# Qwiic_KX134.net
KiCad netlist of a schematic drawn in EAGLE
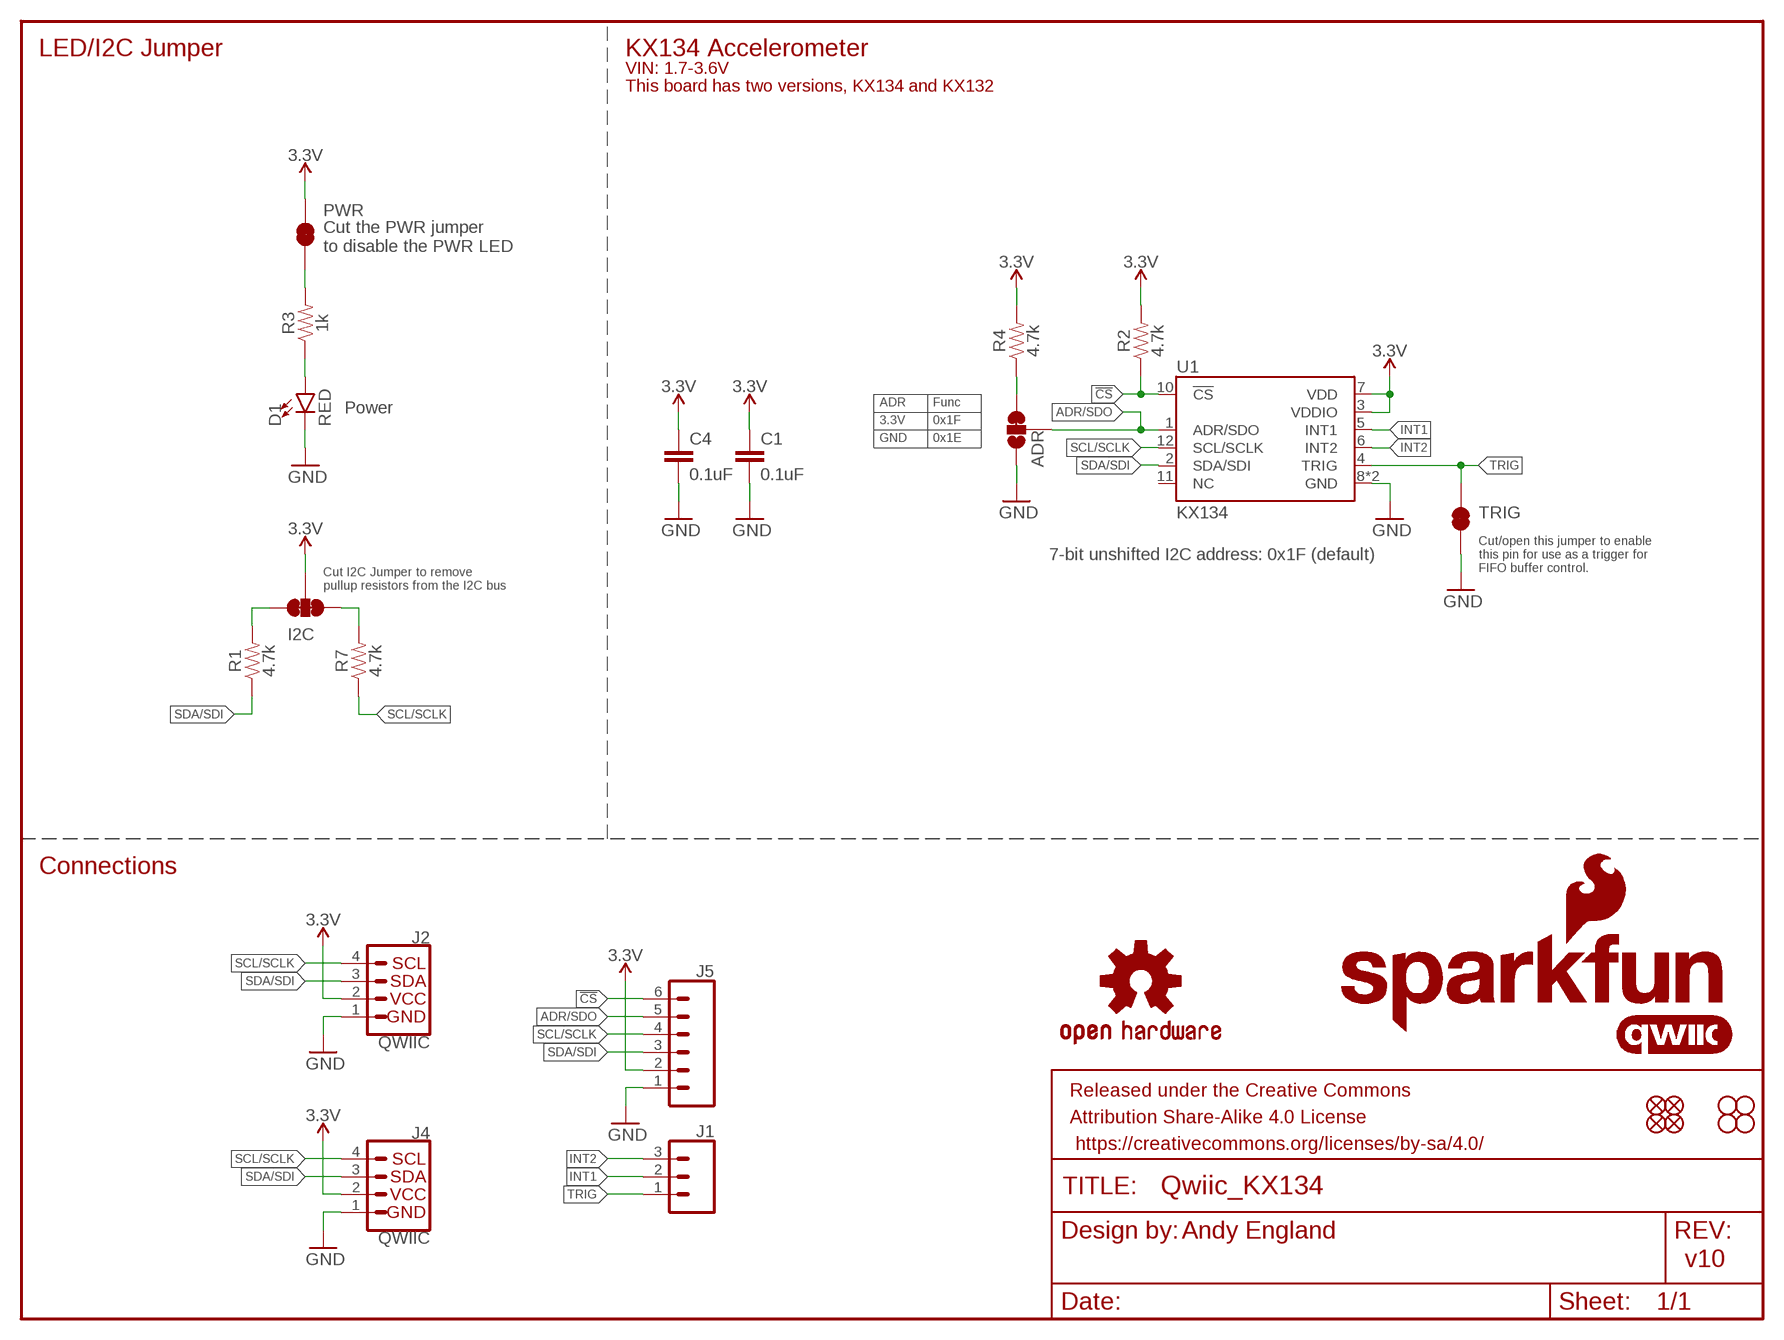
[diagram p0: schematic, sheet 1]

(export (version "E")
  (design (tool "Eeschema 10.0.6"))
  (components
    (comp (ref "ADR")
      (value "JUMPER-SMT_3_1-NC_TRACE_SILK")
      (footprint "eagle-import:SMT-JUMPER_3_1-NC_TRACE_SILK")
      (libsource (lib "eagle-import") (part "JUMPER-SMT_3_1-NC_TRACE_SILK"))
    )
    (comp (ref "C1")
      (value "0.1uF")
      (footprint "eagle-import:0603")
      (libsource (lib "eagle-import") (part "0.1UF-0603-25V-(+80/-20%)"))
    )
    (comp (ref "C4")
      (value "0.1uF")
      (footprint "eagle-import:0603")
      (libsource (lib "eagle-import") (part "0.1UF-0603-25V-(+80/-20%)"))
    )
    (comp (ref "D1")
      (value "RED")
      (footprint "eagle-import:LED-0603")
      (libsource (lib "eagle-import") (part "LED-RED0603"))
    )
    (comp (ref "FRAME1")
      (value "FRAME-LETTER")
      (footprint "eagle-import:CREATIVE_COMMONS")
      (libsource (lib "eagle-import") (part "FRAME-LETTER"))
    )
    (comp (ref "I2C")
      (value "JUMPER-SMT_3_2-NC_TRACE_SILK")
      (footprint "eagle-import:SMT-JUMPER_3_2-NC_TRACE_SILK")
      (libsource (lib "eagle-import") (part "JUMPER-SMT_3_2-NC_TRACE_SILK"))
    )
    (comp (ref "J1")
      (value "CONN_031X03_NO_SILK")
      (footprint "eagle-import:1X03_NO_SILK")
      (libsource (lib "eagle-import") (part "CONN_031X03_NO_SILK"))
    )
    (comp (ref "J2")
      (value "QWIIC")
      (footprint "eagle-import:JST04_1MM_RA")
      (libsource (lib "eagle-import") (part "QWIIC_CONNECTORJS-1MM"))
    )
    (comp (ref "J4")
      (value "QWIIC")
      (footprint "eagle-import:JST04_1MM_RA")
      (libsource (lib "eagle-import") (part "QWIIC_CONNECTORJS-1MM"))
    )
    (comp (ref "J5")
      (value "CONN_06NO_SILK_NO_POP")
      (footprint "eagle-import:1X06_NO_SILK")
      (libsource (lib "eagle-import") (part "CONN_06NO_SILK_NO_POP"))
    )
    (comp (ref "JP1")
      (value "FIDUCIALUFIDUCIAL")
      (footprint "eagle-import:MICRO-FIDUCIAL")
      (libsource (lib "eagle-import") (part "FIDUCIALUFIDUCIAL"))
    )
    (comp (ref "JP2")
      (value "FIDUCIALUFIDUCIAL")
      (footprint "eagle-import:MICRO-FIDUCIAL")
      (libsource (lib "eagle-import") (part "FIDUCIALUFIDUCIAL"))
    )
    (comp (ref "JP3")
      (value "STAND-OFF")
      (footprint "eagle-import:STAND-OFF")
      (libsource (lib "eagle-import") (part "STAND-OFF"))
    )
    (comp (ref "JP4")
      (value "STAND-OFF")
      (footprint "eagle-import:STAND-OFF")
      (libsource (lib "eagle-import") (part "STAND-OFF"))
    )
    (comp (ref "JP5")
      (value "FIDUCIALUFIDUCIAL")
      (footprint "eagle-import:MICRO-FIDUCIAL")
      (libsource (lib "eagle-import") (part "FIDUCIALUFIDUCIAL"))
    )
    (comp (ref "JP6")
      (value "FIDUCIALUFIDUCIAL")
      (footprint "eagle-import:MICRO-FIDUCIAL")
      (libsource (lib "eagle-import") (part "FIDUCIALUFIDUCIAL"))
    )
    (comp (ref "JP7")
      (value "STAND-OFF")
      (footprint "eagle-import:STAND-OFF")
      (libsource (lib "eagle-import") (part "STAND-OFF"))
    )
    (comp (ref "JP8")
      (value "STAND-OFF")
      (footprint "eagle-import:STAND-OFF")
      (libsource (lib "eagle-import") (part "STAND-OFF"))
    )
    (comp (ref "LOGO1")
      (value "SFE_LOGO_FLAME.1_INCH")
      (footprint "eagle-import:SFE_LOGO_FLAME_.1")
      (libsource (lib "eagle-import") (part "SFE_LOGO_FLAME.1_INCH"))
    )
    (comp (ref "LOGO2")
      (value "SFE_LOGO_FLAME.1_INCH")
      (footprint "eagle-import:SFE_LOGO_FLAME_.1")
      (libsource (lib "eagle-import") (part "SFE_LOGO_FLAME.1_INCH"))
    )
    (comp (ref "LOGO3")
      (value "QWIIC_LOGO_4MM")
      (footprint "eagle-import:QWIIC_4MM")
      (libsource (lib "eagle-import") (part "QWIIC_LOGO_4MM"))
    )
    (comp (ref "LOGO4")
      (value "SFE_LOGO_NAME_FLAME.1_INCH")
      (footprint "eagle-import:SFE_LOGO_NAME_FLAME_.1")
      (libsource (lib "eagle-import") (part "SFE_LOGO_NAME_FLAME.1_INCH"))
    )
    (comp (ref "LOGO5")
      (value "OSHW-LOGOS")
      (footprint "eagle-import:OSHW-LOGO-S")
      (libsource (lib "eagle-import") (part "OSHW-LOGOS"))
    )
    (comp (ref "PWR")
      (value "JUMPER-SMT_2_NC_TRACE_SILK")
      (footprint "eagle-import:SMT-JUMPER_2_NC_TRACE_SILK")
      (libsource (lib "eagle-import") (part "JUMPER-SMT_2_NC_TRACE_SILK"))
    )
    (comp (ref "R1")
      (value "4.7k")
      (footprint "eagle-import:0603")
      (libsource (lib "eagle-import") (part "4.7KOHM-0603-1/10W-1%"))
    )
    (comp (ref "R2")
      (value "4.7k")
      (footprint "eagle-import:0603")
      (libsource (lib "eagle-import") (part "4.7KOHM-0603-1/10W-1%"))
    )
    (comp (ref "R3")
      (value "1k")
      (footprint "eagle-import:0603")
      (libsource (lib "eagle-import") (part "1KOHM-0603-1/10W-1%"))
    )
    (comp (ref "R4")
      (value "4.7k")
      (footprint "eagle-import:0603")
      (libsource (lib "eagle-import") (part "4.7KOHM-0603-1/10W-1%"))
    )
    (comp (ref "R7")
      (value "4.7k")
      (footprint "eagle-import:0603")
      (libsource (lib "eagle-import") (part "4.7KOHM-0603-1/10W-1%"))
    )
    (comp (ref "TRIG")
      (value "JUMPER-SMT_2_NC_TRACE_SILK")
      (footprint "eagle-import:SMT-JUMPER_2_NC_TRACE_SILK")
      (libsource (lib "eagle-import") (part "JUMPER-SMT_2_NC_TRACE_SILK"))
    )
    (comp (ref "U1")
      (value "KX134")
      (footprint "eagle-import:KX13X")
      (libsource (lib "eagle-import") (part "KX13X-KX134"))
    )
  )
  (nets
    (net (code "1") (name "/~{CS}") (class "Default")
      (node (ref "J5") (pin "6") (pinfunction "6_6") (pintype "passive"))
      (node (ref "R2") (pin "1") (pinfunction "1_1") (pintype "passive"))
      (node (ref "U1") (pin "10") (pinfunction "~{CS}_10") (pintype "bidirectional"))
    )
    (net (code "2") (name "3.3V") (class "Default")
      (node (ref "C1") (pin "1") (pinfunction "1_1") (pintype "passive"))
      (node (ref "C4") (pin "1") (pinfunction "1_1") (pintype "passive"))
      (node (ref "I2C") (pin "2") (pinfunction "2_2") (pintype "passive"))
      (node (ref "J2") (pin "2") (pinfunction "2_2") (pintype "power_in"))
      (node (ref "J4") (pin "2") (pinfunction "2_2") (pintype "power_in"))
      (node (ref "J5") (pin "2") (pinfunction "2_2") (pintype "passive"))
      (node (ref "PWR") (pin "2") (pinfunction "2_2") (pintype "passive"))
      (node (ref "R2") (pin "2") (pinfunction "2_2") (pintype "passive"))
      (node (ref "R4") (pin "2") (pinfunction "2_2") (pintype "passive"))
      (node (ref "U1") (pin "3") (pinfunction "VDDIO_3") (pintype "bidirectional"))
      (node (ref "U1") (pin "7") (pinfunction "VDD_7") (pintype "bidirectional"))
    )
    (net (code "3") (name "ADR{slash}SDO") (class "Default")
      (node (ref "ADR") (pin "2") (pinfunction "2_2") (pintype "passive"))
      (node (ref "J5") (pin "5") (pinfunction "5_5") (pintype "passive"))
      (node (ref "U1") (pin "1") (pinfunction "ADR/SDO_1") (pintype "bidirectional"))
    )
    (net (code "4") (name "GND") (class "Default")
      (node (ref "ADR") (pin "1") (pinfunction "1_1") (pintype "passive"))
      (node (ref "C1") (pin "2") (pinfunction "2_2") (pintype "passive"))
      (node (ref "C4") (pin "2") (pinfunction "2_2") (pintype "passive"))
      (node (ref "D1") (pin "C") (pinfunction "C_C") (pintype "passive"))
      (node (ref "J2") (pin "1") (pinfunction "1_1") (pintype "power_in"))
      (node (ref "J4") (pin "1") (pinfunction "1_1") (pintype "power_in"))
      (node (ref "J5") (pin "1") (pinfunction "1_1") (pintype "passive"))
      (node (ref "TRIG") (pin "2") (pinfunction "2_2") (pintype "passive"))
      (node (ref "U1") (pin "8") (pinfunction "GND_8") (pintype "bidirectional"))
      (node (ref "U1") (pin "9") (pinfunction "GND_9") (pintype "bidirectional"))
    )
    (net (code "5") (name "INT1") (class "Default")
      (node (ref "J1") (pin "2") (pinfunction "2_2") (pintype "passive"))
      (node (ref "U1") (pin "5") (pinfunction "INT1_5") (pintype "bidirectional"))
    )
    (net (code "6") (name "INT2") (class "Default")
      (node (ref "J1") (pin "3") (pinfunction "3_3") (pintype "passive"))
      (node (ref "U1") (pin "6") (pinfunction "INT2_6") (pintype "bidirectional"))
    )
    (net (code "7") (name "Net-(ADR-Pad3)") (class "Default")
      (node (ref "ADR") (pin "3") (pinfunction "3_3") (pintype "passive"))
      (node (ref "R4") (pin "1") (pinfunction "1_1") (pintype "passive"))
    )
    (net (code "8") (name "Net-(D1-PadA)") (class "Default")
      (node (ref "D1") (pin "A") (pinfunction "A_A") (pintype "passive"))
      (node (ref "R3") (pin "1") (pinfunction "1_1") (pintype "passive"))
    )
    (net (code "9") (name "Net-(I2C-Pad1)") (class "Default")
      (node (ref "I2C") (pin "1") (pinfunction "1_1") (pintype "passive"))
      (node (ref "R7") (pin "2") (pinfunction "2_2") (pintype "passive"))
    )
    (net (code "10") (name "Net-(I2C-Pad3)") (class "Default")
      (node (ref "I2C") (pin "3") (pinfunction "3_3") (pintype "passive"))
      (node (ref "R1") (pin "2") (pinfunction "2_2") (pintype "passive"))
    )
    (net (code "11") (name "Net-(PWR-Pad1)") (class "Default")
      (node (ref "PWR") (pin "1") (pinfunction "1_1") (pintype "passive"))
      (node (ref "R3") (pin "2") (pinfunction "2_2") (pintype "passive"))
    )
    (net (code "12") (name "SCL{slash}SCLK") (class "Default")
      (node (ref "J2") (pin "4") (pinfunction "4_4") (pintype "passive"))
      (node (ref "J4") (pin "4") (pinfunction "4_4") (pintype "passive"))
      (node (ref "J5") (pin "4") (pinfunction "4_4") (pintype "passive"))
      (node (ref "R7") (pin "1") (pinfunction "1_1") (pintype "passive"))
      (node (ref "U1") (pin "12") (pinfunction "SCL/SCLK_12") (pintype "bidirectional"))
    )
    (net (code "13") (name "SDA{slash}SDI") (class "Default")
      (node (ref "J2") (pin "3") (pinfunction "3_3") (pintype "passive"))
      (node (ref "J4") (pin "3") (pinfunction "3_3") (pintype "passive"))
      (node (ref "J5") (pin "3") (pinfunction "3_3") (pintype "passive"))
      (node (ref "R1") (pin "1") (pinfunction "1_1") (pintype "passive"))
      (node (ref "U1") (pin "2") (pinfunction "SDA/SDI_2") (pintype "bidirectional"))
    )
    (net (code "14") (name "TRIG") (class "Default")
      (node (ref "J1") (pin "1") (pinfunction "1_1") (pintype "passive"))
      (node (ref "TRIG") (pin "1") (pinfunction "1_1") (pintype "passive"))
      (node (ref "U1") (pin "4") (pinfunction "TRIG_4") (pintype "bidirectional"))
    )
    (net (code "15") (name "unconnected-(U1-NC-Pad11)") (class "Default")
      (node (ref "U1") (pin "11") (pinfunction "NC_11") (pintype "no_connect"))
    )
  )
)
